# electromag_pwm.net
KiCad netlist of a schematic drawn in EAGLE
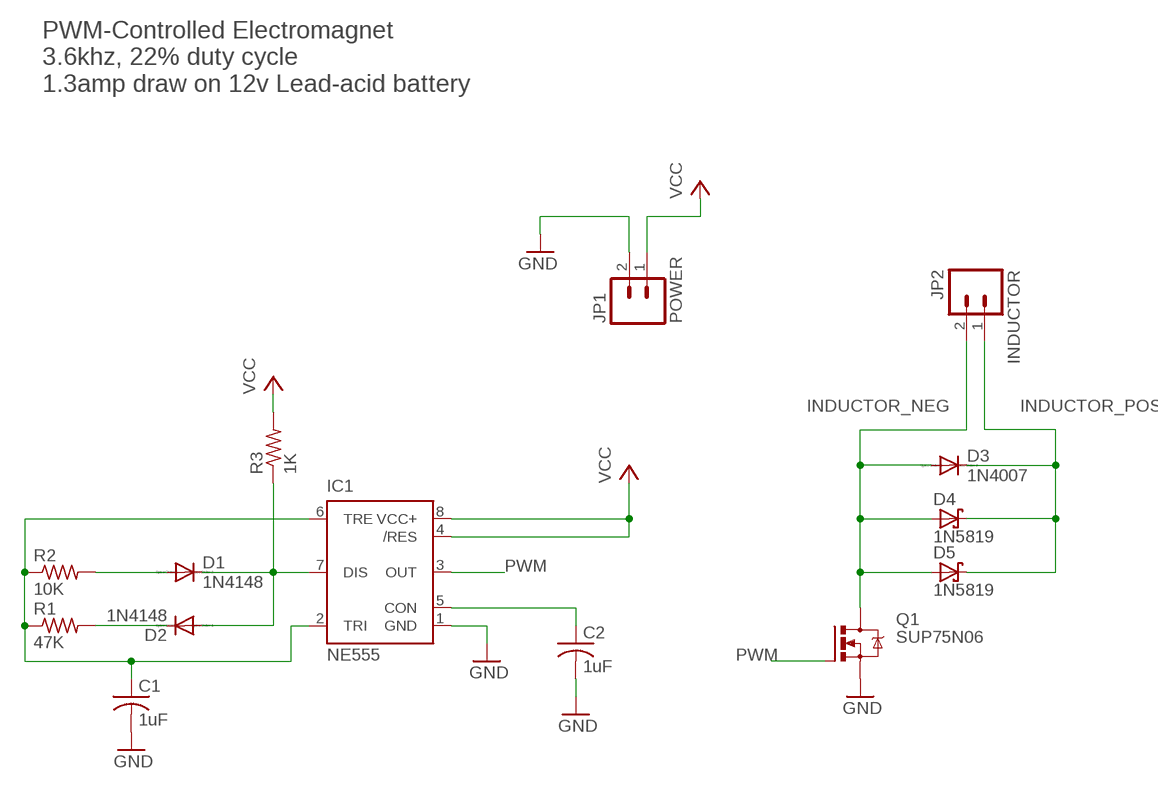
[diagram p0: schematic, sheet 1]

(export (version "E")
  (design (tool "Eeschema 10.0.6"))
  (components
    (comp (ref "C1")
      (value "1uF")
      (footprint "eagle-import:C025-025X050")
      (libsource (lib "eagle-import") (part "C-US025-025X050"))
    )
    (comp (ref "C2")
      (value "1uF")
      (footprint "eagle-import:C025-025X050")
      (libsource (lib "eagle-import") (part "C-US025-025X050"))
    )
    (comp (ref "D1")
      (value "1N4148")
      (footprint "eagle-import:DO35-7")
      (libsource (lib "eagle-import") (part "1N4148DO35-7"))
    )
    (comp (ref "D2")
      (value "1N4148")
      (footprint "eagle-import:DO35-7")
      (libsource (lib "eagle-import") (part "1N4148DO35-7"))
    )
    (comp (ref "D3")
      (value "1N4007")
      (footprint "eagle-import:DO41-10")
      (libsource (lib "eagle-import") (part "1N4004"))
    )
    (comp (ref "D4")
      (value "1N5819")
      (footprint "eagle-import:DO41-7.6")
      (libsource (lib "eagle-import") (part "1N5819-B"))
    )
    (comp (ref "D5")
      (value "1N5819")
      (footprint "eagle-import:DO41-7.6")
      (libsource (lib "eagle-import") (part "1N5819-B"))
    )
    (comp (ref "IC1")
      (value "NE555")
      (footprint "eagle-import:DIL-08")
      (fields (field (name "MF") "Arrow Electronics") (field (name "MPN") "NE555N"))
      (libsource (lib "eagle-import") (part "NE555"))
    )
    (comp (ref "JP1")
      (value "POWER")
      (footprint "eagle-import:JST-2-PTH-VERT")
      (libsource (lib "eagle-import") (part "M02JST-PTH-VERT"))
    )
    (comp (ref "JP2")
      (value "INDUCTOR")
      (footprint "eagle-import:JST-2-PTH-VERT")
      (libsource (lib "eagle-import") (part "M02JST-PTH-VERT"))
    )
    (comp (ref "Q1")
      (value "SUP75N06")
      (footprint "eagle-import:TO220BH")
      (libsource (lib "eagle-import") (part "IRLZ44Z"))
    )
    (comp (ref "R1")
      (value "47K")
      (footprint "eagle-import:0204_5")
      (libsource (lib "eagle-import") (part "R-US_0204/5"))
    )
    (comp (ref "R2")
      (value "10K")
      (footprint "eagle-import:0204_5")
      (libsource (lib "eagle-import") (part "R-US_0204/5"))
    )
    (comp (ref "R3")
      (value "1K")
      (footprint "eagle-import:0204_5")
      (libsource (lib "eagle-import") (part "R-US_0204/5"))
    )
  )
  (nets
    (net (code "1") (name "/INDUCTOR_NEG") (class "Default")
      (node (ref "D3") (pin "A") (pinfunction "A_A") (pintype "passive"))
      (node (ref "D4") (pin "A") (pinfunction "A_A") (pintype "passive"))
      (node (ref "D5") (pin "A") (pinfunction "A_A") (pintype "passive"))
      (node (ref "JP2") (pin "2") (pinfunction "2_2") (pintype "passive"))
      (node (ref "Q1") (pin "D") (pinfunction "D_D") (pintype "passive"))
    )
    (net (code "2") (name "/INDUCTOR_POS") (class "Default")
      (node (ref "D3") (pin "C") (pinfunction "C_C") (pintype "passive"))
      (node (ref "D4") (pin "C") (pinfunction "C_C") (pintype "passive"))
      (node (ref "D5") (pin "C") (pinfunction "C_C") (pintype "passive"))
      (node (ref "JP2") (pin "1") (pinfunction "1_1") (pintype "passive"))
    )
    (net (code "3") (name "/PWM") (class "Default")
      (node (ref "IC1") (pin "3") (pinfunction "OUT_3") (pintype "output"))
      (node (ref "Q1") (pin "G") (pinfunction "G_G") (pintype "passive"))
    )
    (net (code "4") (name "GND") (class "Default")
      (node (ref "C1") (pin "2") (pinfunction "2_2") (pintype "passive"))
      (node (ref "C2") (pin "2") (pinfunction "2_2") (pintype "passive"))
      (node (ref "IC1") (pin "1") (pinfunction "GND_1") (pintype "power_in"))
      (node (ref "JP1") (pin "2") (pinfunction "2_2") (pintype "passive"))
      (node (ref "Q1") (pin "S") (pinfunction "S_S") (pintype "passive"))
    )
    (net (code "5") (name "Net-(D1-PadA)") (class "Default")
      (node (ref "D1") (pin "A") (pinfunction "A_A") (pintype "passive"))
      (node (ref "R2") (pin "2") (pinfunction "2_2") (pintype "passive"))
    )
    (net (code "6") (name "Net-(D2-PadC)") (class "Default")
      (node (ref "D2") (pin "C") (pinfunction "C_C") (pintype "passive"))
      (node (ref "R1") (pin "2") (pinfunction "2_2") (pintype "passive"))
    )
    (net (code "7") (name "Net-(IC1-CON)") (class "Default")
      (node (ref "C2") (pin "1") (pinfunction "1_1") (pintype "passive"))
      (node (ref "IC1") (pin "5") (pinfunction "CON_5") (pintype "input"))
    )
    (net (code "8") (name "Net-(IC1-DIS)") (class "Default")
      (node (ref "D1") (pin "C") (pinfunction "C_C") (pintype "passive"))
      (node (ref "D2") (pin "A") (pinfunction "A_A") (pintype "passive"))
      (node (ref "IC1") (pin "7") (pinfunction "DIS_7") (pintype "input"))
      (node (ref "R3") (pin "1") (pinfunction "1_1") (pintype "passive"))
    )
    (net (code "9") (name "Net-(IC1-TRE)") (class "Default")
      (node (ref "C1") (pin "1") (pinfunction "1_1") (pintype "passive"))
      (node (ref "IC1") (pin "2") (pinfunction "TRI_2") (pintype "input"))
      (node (ref "IC1") (pin "6") (pinfunction "TRE_6") (pintype "input"))
      (node (ref "R1") (pin "1") (pinfunction "1_1") (pintype "passive"))
      (node (ref "R2") (pin "1") (pinfunction "1_1") (pintype "passive"))
    )
    (net (code "10") (name "VCC") (class "Default")
      (node (ref "IC1") (pin "4") (pinfunction "/RES_4") (pintype "input"))
      (node (ref "IC1") (pin "8") (pinfunction "VCC+_8") (pintype "power_in"))
      (node (ref "JP1") (pin "1") (pinfunction "1_1") (pintype "passive"))
      (node (ref "R3") (pin "2") (pinfunction "2_2") (pintype "passive"))
    )
  )
)
